# PowerDistribution.net
KiCad netlist of a schematic drawn in Altium Designer
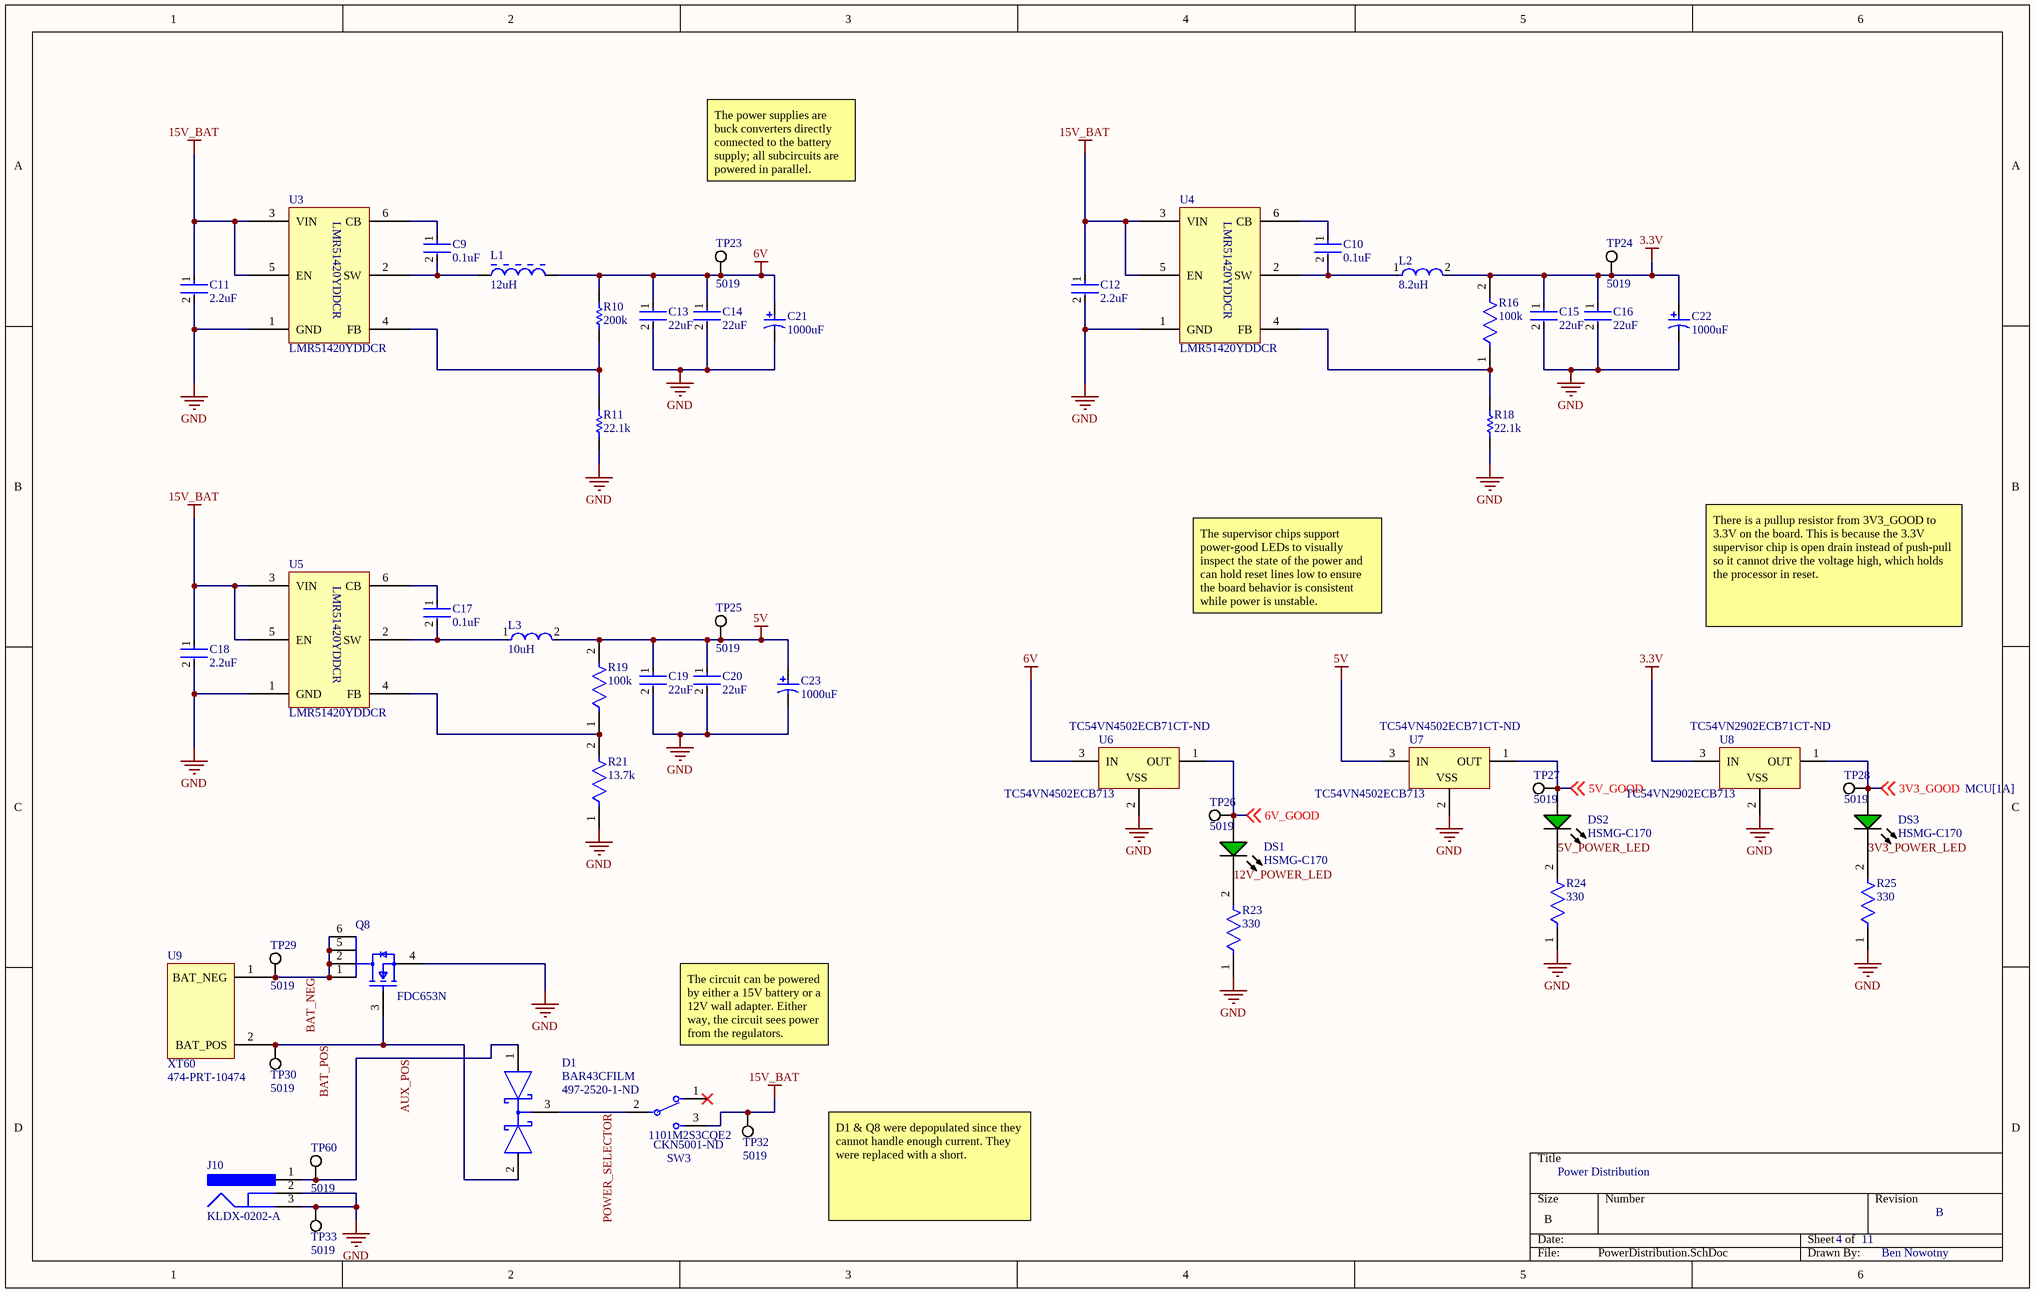
[diagram p0: PowerDistribution.SchDoc]

(export (version "E")
  (design (tool "Eeschema 10.0.6"))
  (components
    (comp (ref "C9")
      (value "0.1uF")
      (footprint "FP-CC0805-0_85-MFG")
      (description "CAP CER 0.1UF 25V X7R 0805")
      (fields (field (name "MANUFACTURER PART NUMBER") "CC0805KRX7R8BB104") (field (name "TOLERANCE") "0.1"))
      (libsource (lib "Altium Content Vault") (part "11868f565c42a9108669ba33697ecf6"))
    )
    (comp (ref "C10")
      (value "0.1uF")
      (footprint "FP-CC0805-0_85-MFG")
      (description "CAP CER 0.1UF 25V X7R 0805")
      (fields (field (name "MANUFACTURER PART NUMBER") "CC0805KRX7R8BB104") (field (name "TOLERANCE") "0.1"))
      (libsource (lib "Altium Content Vault") (part "11868f565c42a9108669ba33697ecf6"))
    )
    (comp (ref "C11")
      (value "2.2uF")
      (footprint "FP-CGA4J-IPC_A")
      (description "Cap Ceramic 2.2uF 35V X7R 10% Pad SMD 0805 +125°C Automotive T/R")
      (fields (field (name "TOLERANCE") "10%") (field (name "MANUFACTURER") "TDK"))
      (libsource (lib "Altium Content Vault") (part "b4654b650e69147ec39a6b967a45e02"))
    )
    (comp (ref "C12")
      (value "2.2uF")
      (footprint "FP-CGA4J-IPC_A")
      (description "Cap Ceramic 2.2uF 35V X7R 10% Pad SMD 0805 +125°C Automotive T/R")
      (fields (field (name "TOLERANCE") "10%") (field (name "MANUFACTURER") "TDK"))
      (libsource (lib "Altium Content Vault") (part "b4654b650e69147ec39a6b967a45e02"))
    )
    (comp (ref "C13")
      (value "22uF")
      (footprint "FP-GRM21B-0_2-e0_2_0_7-IPC_B")
      (description "Chip Multilayer Ceramic Capacitors for General Purpose, 0805, 22uF, X5R, 15%, 20%, 25V")
      (fields (field (name "TOLERANCE") "20%") (field (name "VOLTAGE") "25V"))
      (libsource (lib "Altium Content Vault") (part "b4654b650e69147ec39a6b967a45e02"))
    )
    (comp (ref "C14")
      (value "22uF")
      (footprint "FP-GRM21B-0_2-e0_2_0_7-IPC_B")
      (description "Chip Multilayer Ceramic Capacitors for General Purpose, 0805, 22uF, X5R, 15%, 20%, 25V")
      (fields (field (name "TOLERANCE") "20%") (field (name "VOLTAGE") "25V"))
      (libsource (lib "Altium Content Vault") (part "b4654b650e69147ec39a6b967a45e02"))
    )
    (comp (ref "C15")
      (value "22uF")
      (footprint "FP-GRM21B-0_2-e0_2_0_7-IPC_B")
      (description "Chip Multilayer Ceramic Capacitors for General Purpose, 0805, 22uF, X5R, 15%, 20%, 25V")
      (fields (field (name "TOLERANCE") "20%") (field (name "VOLTAGE") "25V"))
      (libsource (lib "Altium Content Vault") (part "b4654b650e69147ec39a6b967a45e02"))
    )
    (comp (ref "C16")
      (value "22uF")
      (footprint "FP-GRM21B-0_2-e0_2_0_7-IPC_B")
      (description "Chip Multilayer Ceramic Capacitors for General Purpose, 0805, 22uF, X5R, 15%, 20%, 25V")
      (fields (field (name "TOLERANCE") "20%") (field (name "VOLTAGE") "25V"))
      (libsource (lib "Altium Content Vault") (part "b4654b650e69147ec39a6b967a45e02"))
    )
    (comp (ref "C17")
      (value "0.1uF")
      (footprint "FP-CC0805-0_85-MFG")
      (description "CAP CER 0.1UF 25V X7R 0805")
      (fields (field (name "MANUFACTURER PART NUMBER") "CC0805KRX7R8BB104") (field (name "TOLERANCE") "0.1"))
      (libsource (lib "Altium Content Vault") (part "11868f565c42a9108669ba33697ecf6"))
    )
    (comp (ref "C18")
      (value "2.2uF")
      (footprint "FP-CGA4J-IPC_A")
      (description "Cap Ceramic 2.2uF 35V X7R 10% Pad SMD 0805 +125°C Automotive T/R")
      (fields (field (name "TOLERANCE") "10%") (field (name "MANUFACTURER") "TDK"))
      (libsource (lib "Altium Content Vault") (part "b4654b650e69147ec39a6b967a45e02"))
    )
    (comp (ref "C19")
      (value "22uF")
      (footprint "FP-GRM21B-0_2-e0_2_0_7-IPC_B")
      (description "Chip Multilayer Ceramic Capacitors for General Purpose, 0805, 22uF, X5R, 15%, 20%, 25V")
      (fields (field (name "TOLERANCE") "20%") (field (name "VOLTAGE") "25V"))
      (libsource (lib "Altium Content Vault") (part "b4654b650e69147ec39a6b967a45e02"))
    )
    (comp (ref "C20")
      (value "22uF")
      (footprint "FP-GRM21B-0_2-e0_2_0_7-IPC_B")
      (description "Chip Multilayer Ceramic Capacitors for General Purpose, 0805, 22uF, X5R, 15%, 20%, 25V")
      (fields (field (name "TOLERANCE") "20%") (field (name "VOLTAGE") "25V"))
      (libsource (lib "Altium Content Vault") (part "b4654b650e69147ec39a6b967a45e02"))
    )
    (comp (ref "C21")
      (value "1000uF")
      (footprint "NIC-CAPA2-10X10_V")
      (fields
        (field (name "MANUFACTURER") "Nichicon")
        (field (name "PARTNUMBER") "UUD1A102MNL1GS")
        (field (name "TOLERANCE") "20%")
      )
      (libsource (lib "Altium Content Vault") (part "NIC-CAP-P-2"))
    )
    (comp (ref "C22")
      (value "1000uF")
      (footprint "NIC-CAPA2-10X10_V")
      (fields
        (field (name "MANUFACTURER") "Nichicon")
        (field (name "PARTNUMBER") "UUD1A102MNL1GS")
        (field (name "TOLERANCE") "20%")
      )
      (libsource (lib "Altium Content Vault") (part "NIC-CAP-P-2"))
    )
    (comp (ref "C23")
      (value "1000uF")
      (footprint "NIC-CAPA2-10X10_V")
      (fields
        (field (name "MANUFACTURER") "Nichicon")
        (field (name "PARTNUMBER") "UUD1A102MNL1GS")
        (field (name "TOLERANCE") "20%")
      )
      (libsource (lib "Altium Content Vault") (part "NIC-CAP-P-2"))
    )
    (comp (ref "D1")
      (value "BAR43CFILM")
      (footprint "FP-SOT23-3L-MFG")
      (description "DIODE ARRAY SCHOTTKY 30V SOT23-3")
      (fields
        (field (name "OCTOPART") "https://octopart.com/bar43cfilm-stmicroelectronics-39683191")
        (field (name "MANUFACTURER") "STMicroelectronics")
        (field (name "SUPPLIER PART NUMBER 1") "497-2520-1-ND")
      )
      (libsource (lib "Altium Content Vault") (part "680c0165bcb2da9b6dd4f4f2387c35b"))
    )
    (comp (ref "DS1")
      (value "HSMG-C170")
      (footprint "AVAG-HSMX-C170_V")
      (description "Chip LED, Green, 2.2 V, -40 to 85 degC, 2-Pin SMD, Pb-Free, Tape and Reel")
      (fields (field (name "MANUFACTURER") "Avago"))
      (libsource (lib "Altium Content Vault") (part "LED_GREEN_A1K2-2"))
    )
    (comp (ref "DS2")
      (value "HSMG-C170")
      (footprint "AVAG-HSMX-C170_V")
      (description "Chip LED, Green, 2.2 V, -40 to 85 degC, 2-Pin SMD, Pb-Free, Tape and Reel")
      (fields (field (name "MANUFACTURER") "Avago"))
      (libsource (lib "Altium Content Vault") (part "LED_GREEN_A1K2-2"))
    )
    (comp (ref "DS3")
      (value "HSMG-C170")
      (footprint "AVAG-HSMX-C170_V")
      (description "Chip LED, Green, 2.2 V, -40 to 85 degC, 2-Pin SMD, Pb-Free, Tape and Reel")
      (fields (field (name "MANUFACTURER") "Avago"))
      (libsource (lib "Altium Content Vault") (part "LED_GREEN_A1K2-2"))
    )
    (comp (ref "J10")
      (value "KLDX-0202-A")
      (footprint "KYCN-KLDX-0202-A_V")
      (description "DC Power Jack, 24 V, 3.5 A, -25 to 85 degC, 3-Pin THD, RoHS")
      (fields (field (name "MANUFACTURER") "Kycon"))
      (libsource (lib "Altium Content Vault") (part "JACK-2CD3-RN"))
    )
    (comp (ref "L1")
      (value "12uH")
      (footprint "BOUR-SDR0403-2_V")
      (fields
        (field (name "PARTNUMBER") "SDR0403-120ML")
        (field (name "MANUFACTURER") "Bourns")
        (field (name "TOLERANCE") "20%")
      )
      (libsource (lib "Altium Content Vault") (part "BOUR-IND-2A"))
    )
    (comp (ref "L2")
      (value "8.2uH")
      (footprint "FP-SRP4020TA-MFG")
      (description "FIXED IND 8.2UH 2A 180 MOHM SMD")
      (fields (field (name "MANUFACTURER") "Bourns") (field (name "TOLERANCE") "20%"))
      (libsource (lib "Altium Content Vault") (part "725321dda6339637d4d059423bc1c3c"))
    )
    (comp (ref "L3")
      (value "10uH")
      (footprint "FP-LB2012-1_25-0_2-MFG")
      (description "SMD Inductors 10uH ±10% 0.15A 0.468Ω 0805")
      (fields (field (name "TOLERANCE") "10%") (field (name "MANUFACTURER") "Taiyo Yuden"))
      (libsource (lib "Altium Content Vault") (part "725321dda6339637d4d059423bc1c3c"))
    )
    (comp (ref "Q8")
      (value "FDC653N")
      (footprint "FP-419BL-MFG")
      (description "MOSFET N-CH 30V 5A SSOT-6")
      (fields
        (field (name "MANUFACTURER") "ON Semiconductor")
        (field (name "OCTOPART") "https://octopart.com/fdc653n-on+semiconductor-84325763")
      )
      (libsource (lib "Altium Content Vault") (part "564475a1266d674ca215bf0a31b2b4c"))
    )
    (comp (ref "R10")
      (value "200k")
      (footprint "RESC2013X50X30NL20T20")
      (fields
        (field (name "PART NUMBER") "CRCW0805200KFKEA")
        (field (name "MANUFACTURER") "Vishay Dale")
        (field (name "TOLERANCE") "1%")
      )
      (libsource (lib "Altium Content Vault") (part "RES"))
    )
    (comp (ref "R11")
      (value "22.1k")
      (footprint "RESC2013X70X40NL20T20")
      (fields
        (field (name "PART NUMBER") "ERJ-6ENF2212V")
        (field (name "MANUFACTURER") "Panasonic")
        (field (name "TOLERANCE") "1%")
      )
      (libsource (lib "Altium Content Vault") (part "RES"))
    )
    (comp (ref "R16")
      (value "100k")
      (footprint "FP-RC0805-0_6-IPC_C")
      (description "RES 100K OHM 1% 1/8W 0805")
      (fields (field (name "TOLERANCE") "1%") (field (name "MANUFACTURER") "Yageo"))
      (libsource (lib "Altium Content Vault") (part "1029c3af85768c4190bb7ad29bc67b5"))
    )
    (comp (ref "R18")
      (value "22.1k")
      (footprint "RESC2013X70X40NL20T20")
      (fields
        (field (name "PART NUMBER") "ERJ-6ENF2212V")
        (field (name "MANUFACTURER") "Panasonic")
        (field (name "TOLERANCE") "1%")
      )
      (libsource (lib "Altium Content Vault") (part "RES"))
    )
    (comp (ref "R19")
      (value "100k")
      (footprint "FP-RC0805-0_6-IPC_C")
      (description "RES 100K OHM 1% 1/8W 0805")
      (fields (field (name "TOLERANCE") "1%") (field (name "MANUFACTURER") "Yageo"))
      (libsource (lib "Altium Content Vault") (part "1029c3af85768c4190bb7ad29bc67b5"))
    )
    (comp (ref "R21")
      (value "13.7k")
      (footprint "FP-CRCW0805-e3-IPC_A")
      (description "RES Thick Film, 13.7kΩ, 1%, 0.125W, 100ppm/°C, 0805")
      (fields (field (name "TOLERANCE") "1%") (field (name "MANUFACTURER") "Vishay"))
      (libsource (lib "Altium Content Vault") (part "1029c3af85768c4190bb7ad29bc67b5"))
    )
    (comp (ref "R23")
      (value "330")
      (footprint "FP-CRCW0805-e3-MFG")
      (description "RES Thick Film, 330Ω, 1%, 0.125W, 100ppm/°C, 0805")
      (fields (field (name "TOLERANCE") "1%") (field (name "MANUFACTURER") "Vishay"))
      (libsource (lib "Altium Content Vault") (part "1029c3af85768c4190bb7ad29bc67b5"))
    )
    (comp (ref "R24")
      (value "330")
      (footprint "FP-CRCW0805-e3-MFG")
      (description "RES Thick Film, 330Ω, 1%, 0.125W, 100ppm/°C, 0805")
      (fields (field (name "TOLERANCE") "1%") (field (name "MANUFACTURER") "Vishay"))
      (libsource (lib "Altium Content Vault") (part "1029c3af85768c4190bb7ad29bc67b5"))
    )
    (comp (ref "R25")
      (value "330")
      (footprint "FP-CRCW0805-e3-MFG")
      (description "RES Thick Film, 330Ω, 1%, 0.125W, 100ppm/°C, 0805")
      (fields (field (name "TOLERANCE") "1%") (field (name "MANUFACTURER") "Vishay"))
      (libsource (lib "Altium Content Vault") (part "1029c3af85768c4190bb7ad29bc67b5"))
    )
    (comp (ref "SW3")
      (value "1101M2S3CQE2")
      (footprint "FP-1101M2S3CQE2-MFG")
      (description "SWITCH SLIDE SPDT 6A 120V")
      (fields (field (name "SUPPLIER PART NUMBER 1") "CKN5001-ND") (field (name "MANUFACTURER") "ITT C&K"))
      (libsource (lib "Altium Content Vault") (part "7fcaa069a19c2acd609832313418d7c"))
    )
    (comp (ref "TP23")
      (value "5019")
      (footprint "KSTN-5019_V")
      (description "Test Point, 1 Position SMD, RoHS, Tape and Reel")
      (fields (field (name "MANUFACTURER") "Keystone Electronics"))
      (libsource (lib "Altium Content Vault") (part "TESTPOINT_WHITE"))
    )
    (comp (ref "TP24")
      (value "5019")
      (footprint "KSTN-5019_V")
      (description "Test Point, 1 Position SMD, RoHS, Tape and Reel")
      (fields (field (name "MANUFACTURER") "Keystone Electronics"))
      (libsource (lib "Altium Content Vault") (part "TESTPOINT_WHITE"))
    )
    (comp (ref "TP25")
      (value "5019")
      (footprint "KSTN-5019_V")
      (description "Test Point, 1 Position SMD, RoHS, Tape and Reel")
      (fields (field (name "MANUFACTURER") "Keystone Electronics"))
      (libsource (lib "Altium Content Vault") (part "TESTPOINT_WHITE"))
    )
    (comp (ref "TP26")
      (value "5019")
      (footprint "KSTN-5019_V")
      (description "Test Point, 1 Position SMD, RoHS, Tape and Reel")
      (fields (field (name "MANUFACTURER") "Keystone Electronics"))
      (libsource (lib "Altium Content Vault") (part "TESTPOINT_WHITE"))
    )
    (comp (ref "TP27")
      (value "5019")
      (footprint "KSTN-5019_V")
      (description "Test Point, 1 Position SMD, RoHS, Tape and Reel")
      (fields (field (name "MANUFACTURER") "Keystone Electronics"))
      (libsource (lib "Altium Content Vault") (part "TESTPOINT_WHITE"))
    )
    (comp (ref "TP28")
      (value "5019")
      (footprint "KSTN-5019_V")
      (description "Test Point, 1 Position SMD, RoHS, Tape and Reel")
      (fields (field (name "MANUFACTURER") "Keystone Electronics"))
      (libsource (lib "Altium Content Vault") (part "TESTPOINT_WHITE"))
    )
    (comp (ref "TP29")
      (value "5019")
      (footprint "KSTN-5019_V")
      (description "Test Point, 1 Position SMD, RoHS, Tape and Reel")
      (fields (field (name "MANUFACTURER") "Keystone Electronics"))
      (libsource (lib "Altium Content Vault") (part "TESTPOINT_WHITE"))
    )
    (comp (ref "TP30")
      (value "5019")
      (footprint "KSTN-5019_V")
      (description "Test Point, 1 Position SMD, RoHS, Tape and Reel")
      (fields (field (name "MANUFACTURER") "Keystone Electronics"))
      (libsource (lib "Altium Content Vault") (part "TESTPOINT_WHITE"))
    )
    (comp (ref "TP32")
      (value "5019")
      (footprint "KSTN-5019_V")
      (description "Test Point, 1 Position SMD, RoHS, Tape and Reel")
      (fields (field (name "MANUFACTURER") "Keystone Electronics"))
      (libsource (lib "Altium Content Vault") (part "TESTPOINT_WHITE"))
    )
    (comp (ref "TP33")
      (value "5019")
      (footprint "KSTN-5019_V")
      (description "Test Point, 1 Position SMD, RoHS, Tape and Reel")
      (fields (field (name "MANUFACTURER") "Keystone Electronics"))
      (libsource (lib "Altium Content Vault") (part "TESTPOINT_WHITE"))
    )
    (comp (ref "TP60")
      (value "5019")
      (footprint "KSTN-5019_V")
      (description "Test Point, 1 Position SMD, RoHS, Tape and Reel")
      (fields (field (name "MANUFACTURER") "Keystone Electronics"))
      (libsource (lib "Altium Content Vault") (part "TESTPOINT_WHITE"))
    )
    (comp (ref "U3")
      (value "LMR51420YDDCR")
      (footprint "BUCK_REG_FOOTPRINT_SOT95P280X110-6N")
      (fields (field (name "MANUFACTURER") "Texas Instruments"))
      (libsource (lib "CustomSchematics") (part "LMR51420YDDCR"))
    )
    (comp (ref "U4")
      (value "LMR51420YDDCR")
      (footprint "BUCK_REG_FOOTPRINT_SOT95P280X110-6N")
      (fields (field (name "MANUFACTURER") "Texas Instruments"))
      (libsource (lib "CustomSchematics") (part "LMR51420YDDCR"))
    )
    (comp (ref "U5")
      (value "LMR51420YDDCR")
      (footprint "BUCK_REG_FOOTPRINT_SOT95P280X110-6N")
      (fields (field (name "MANUFACTURER") "Texas Instruments"))
      (libsource (lib "CustomSchematics") (part "LMR51420YDDCR"))
    )
    (comp (ref "U6")
      (value "TC54VN4502ECB713")
      (footprint "SOT-23A-CB3_L")
      (fields
        (field (name "SUPPLIER PART NUMBER 1") "TC54VN4502ECB71CT-ND")
        (field (name "MANUFACTURER") "Microchip")
      )
      (libsource (lib "Altium Content Vault") (part "PM-VLTD-TC51N2202-SOT3"))
    )
    (comp (ref "U7")
      (value "TC54VN4502ECB713")
      (footprint "SOT-23A-CB3_L")
      (fields
        (field (name "SUPPLIER PART NUMBER 1") "TC54VN4502ECB71CT-ND")
        (field (name "MANUFACTURER") "Microchip")
      )
      (libsource (lib "Altium Content Vault") (part "PM-VLTD-TC51N2202-SOT3"))
    )
    (comp (ref "U8")
      (value "TC54VN2902ECB713")
      (footprint "SOT-23A-CB3_L")
      (fields
        (field (name "SUPPLIER PART NUMBER 1") "TC54VN2902ECB71CT-ND")
        (field (name "MANUFACTURER") "Microchip")
      )
      (libsource (lib "Altium Content Vault") (part "PM-VLTD-TC51N2202-SOT3"))
    )
    (comp (ref "U9")
      (value "XT60")
      (footprint "XT60")
      (description "XT60 Connectors Male/female Pair")
      (fields
        (field (name "MANUFACTURER") "SparkFun")
        (field (name "MANUFACTURER PART NUMBER") "PRT-10474")
        (field (name "SUPPLIER PART NUMBER 1") "474-PRT-10474")
      )
      (libsource (lib "CustomSchematics") (part "XT60"))
    )
  )
  (nets
    (net (code "1") (name "/3V3_POWER_LED") (class "Default")
      (node (ref "DS3") (pin "2") (pinfunction "K_2") (pintype "passive"))
      (node (ref "R25") (pin "2") (pinfunction "2_2") (pintype "passive"))
    )
    (net (code "2") (name "/5V_POWER_LED") (class "Default")
      (node (ref "DS2") (pin "2") (pinfunction "K_2") (pintype "passive"))
      (node (ref "R24") (pin "2") (pinfunction "2_2") (pintype "passive"))
    )
    (net (code "3") (name "/12V_POWER_LED") (class "Default")
      (node (ref "DS1") (pin "2") (pinfunction "K_2") (pintype "passive"))
      (node (ref "R23") (pin "2") (pinfunction "2_2") (pintype "passive"))
    )
    (net (code "4") (name "/AUX_POS") (class "Default")
      (node (ref "D1") (pin "1") (pinfunction "A1_1") (pintype "passive"))
      (node (ref "J10") (pin "1") (pinfunction "1_1") (pintype "passive"))
      (node (ref "TP60") (pin "1") (pinfunction "1_1") (pintype "passive"))
    )
    (net (code "5") (name "/BAT_NEG") (class "Default")
      (node (ref "Q8") (pin "1") (pinfunction "D_1") (pintype "passive"))
      (node (ref "Q8") (pin "2") (pinfunction "D_2") (pintype "passive"))
      (node (ref "Q8") (pin "5") (pinfunction "D_5") (pintype "passive"))
      (node (ref "Q8") (pin "6") (pinfunction "D_6") (pintype "passive"))
      (node (ref "TP29") (pin "1") (pinfunction "1_1") (pintype "passive"))
      (node (ref "U9") (pin "1") (pinfunction "BAT_NEG_1") (pintype "passive"))
    )
    (net (code "6") (name "/BAT_POS") (class "Default")
      (node (ref "D1") (pin "2") (pinfunction "A2_2") (pintype "passive"))
      (node (ref "Q8") (pin "3") (pinfunction "G_3") (pintype "passive"))
      (node (ref "TP30") (pin "1") (pinfunction "1_1") (pintype "passive"))
      (node (ref "U9") (pin "2") (pinfunction "BAT_POS_2") (pintype "passive"))
    )
    (net (code "7") (name "/POWER_SELECTOR") (class "Default")
      (node (ref "D1") (pin "3") (pinfunction "K_3") (pintype "passive"))
      (node (ref "SW3") (pin "2") (pinfunction "COMM_2") (pintype "passive"))
    )
    (net (code "8") (name "3.3V") (class "Default")
      (node (ref "C15") (pin "1") (pinfunction "1_1") (pintype "passive"))
      (node (ref "C16") (pin "1") (pinfunction "1_1") (pintype "passive"))
      (node (ref "C22") (pin "1") (pinfunction "1_1") (pintype "passive"))
      (node (ref "L2") (pin "2") (pinfunction "2_2") (pintype "passive"))
      (node (ref "R16") (pin "2") (pinfunction "2_2") (pintype "passive"))
      (node (ref "TP24") (pin "1") (pinfunction "1_1") (pintype "passive"))
      (node (ref "U8") (pin "3") (pinfunction "IN_3") (pintype "power_in"))
    )
    (net (code "9") (name "3V3_GOOD") (class "Default")
      (node (ref "DS3") (pin "1") (pinfunction "A_1") (pintype "passive"))
      (node (ref "TP28") (pin "1") (pinfunction "1_1") (pintype "passive"))
      (node (ref "U8") (pin "1") (pinfunction "OUT_1") (pintype "power_in"))
    )
    (net (code "10") (name "5V") (class "Default")
      (node (ref "C19") (pin "1") (pinfunction "1_1") (pintype "passive"))
      (node (ref "C20") (pin "1") (pinfunction "1_1") (pintype "passive"))
      (node (ref "C23") (pin "1") (pinfunction "1_1") (pintype "passive"))
      (node (ref "L3") (pin "2") (pinfunction "2_2") (pintype "passive"))
      (node (ref "R19") (pin "2") (pinfunction "2_2") (pintype "passive"))
      (node (ref "TP25") (pin "1") (pinfunction "1_1") (pintype "passive"))
      (node (ref "U7") (pin "3") (pinfunction "IN_3") (pintype "power_in"))
    )
    (net (code "11") (name "5V_GOOD") (class "Default")
      (node (ref "DS2") (pin "1") (pinfunction "A_1") (pintype "passive"))
      (node (ref "TP27") (pin "1") (pinfunction "1_1") (pintype "passive"))
      (node (ref "U7") (pin "1") (pinfunction "OUT_1") (pintype "power_in"))
    )
    (net (code "12") (name "6V") (class "Default")
      (node (ref "C13") (pin "1") (pinfunction "1_1") (pintype "passive"))
      (node (ref "C14") (pin "1") (pinfunction "1_1") (pintype "passive"))
      (node (ref "C21") (pin "1") (pinfunction "1_1") (pintype "passive"))
      (node (ref "L1") (pin "2") (pinfunction "2_2") (pintype "passive"))
      (node (ref "R10") (pin "2") (pinfunction "2_2") (pintype "passive"))
      (node (ref "TP23") (pin "1") (pinfunction "1_1") (pintype "passive"))
      (node (ref "U6") (pin "3") (pinfunction "IN_3") (pintype "power_in"))
    )
    (net (code "13") (name "6V_GOOD") (class "Default")
      (node (ref "DS1") (pin "1") (pinfunction "A_1") (pintype "passive"))
      (node (ref "TP26") (pin "1") (pinfunction "1_1") (pintype "passive"))
      (node (ref "U6") (pin "1") (pinfunction "OUT_1") (pintype "power_in"))
    )
    (net (code "14") (name "15V_BAT") (class "Default")
      (node (ref "C11") (pin "1") (pinfunction "1_1") (pintype "passive"))
      (node (ref "C12") (pin "1") (pinfunction "1_1") (pintype "passive"))
      (node (ref "C18") (pin "1") (pinfunction "1_1") (pintype "passive"))
      (node (ref "SW3") (pin "3") (pinfunction "3_3") (pintype "passive"))
      (node (ref "TP32") (pin "1") (pinfunction "1_1") (pintype "passive"))
      (node (ref "U3") (pin "3") (pinfunction "VIN_3") (pintype "passive"))
      (node (ref "U3") (pin "5") (pinfunction "EN_5") (pintype "passive"))
      (node (ref "U4") (pin "3") (pinfunction "VIN_3") (pintype "passive"))
      (node (ref "U4") (pin "5") (pinfunction "EN_5") (pintype "passive"))
      (node (ref "U5") (pin "3") (pinfunction "VIN_3") (pintype "passive"))
      (node (ref "U5") (pin "5") (pinfunction "EN_5") (pintype "passive"))
    )
    (net (code "15") (name "GND") (class "Default")
      (node (ref "C11") (pin "2") (pinfunction "2_2") (pintype "passive"))
      (node (ref "C12") (pin "2") (pinfunction "2_2") (pintype "passive"))
      (node (ref "C13") (pin "2") (pinfunction "2_2") (pintype "passive"))
      (node (ref "C14") (pin "2") (pinfunction "2_2") (pintype "passive"))
      (node (ref "C15") (pin "2") (pinfunction "2_2") (pintype "passive"))
      (node (ref "C16") (pin "2") (pinfunction "2_2") (pintype "passive"))
      (node (ref "C18") (pin "2") (pinfunction "2_2") (pintype "passive"))
      (node (ref "C19") (pin "2") (pinfunction "2_2") (pintype "passive"))
      (node (ref "C20") (pin "2") (pinfunction "2_2") (pintype "passive"))
      (node (ref "C21") (pin "2") (pinfunction "2_2") (pintype "passive"))
      (node (ref "C22") (pin "2") (pinfunction "2_2") (pintype "passive"))
      (node (ref "C23") (pin "2") (pinfunction "2_2") (pintype "passive"))
      (node (ref "J10") (pin "2") (pinfunction "2_2") (pintype "passive"))
      (node (ref "J10") (pin "3") (pinfunction "3_3") (pintype "passive"))
      (node (ref "Q8") (pin "4") (pinfunction "S_4") (pintype "passive"))
      (node (ref "R11") (pin "1") (pinfunction "1_1") (pintype "passive"))
      (node (ref "R18") (pin "1") (pinfunction "1_1") (pintype "passive"))
      (node (ref "R21") (pin "1") (pinfunction "1_1") (pintype "passive"))
      (node (ref "R23") (pin "1") (pinfunction "1_1") (pintype "passive"))
      (node (ref "R24") (pin "1") (pinfunction "1_1") (pintype "passive"))
      (node (ref "R25") (pin "1") (pinfunction "1_1") (pintype "passive"))
      (node (ref "TP33") (pin "1") (pinfunction "1_1") (pintype "passive"))
      (node (ref "U3") (pin "1") (pinfunction "GND_1") (pintype "passive"))
      (node (ref "U4") (pin "1") (pinfunction "GND_1") (pintype "passive"))
      (node (ref "U5") (pin "1") (pinfunction "GND_1") (pintype "passive"))
      (node (ref "U6") (pin "2") (pinfunction "VSS_2") (pintype "power_in"))
      (node (ref "U7") (pin "2") (pinfunction "VSS_2") (pintype "power_in"))
      (node (ref "U8") (pin "2") (pinfunction "VSS_2") (pintype "power_in"))
    )
    (net (code "16") (name "Net-(U3-CB)") (class "Default")
      (node (ref "C9") (pin "1") (pinfunction "1_1") (pintype "passive"))
      (node (ref "U3") (pin "6") (pinfunction "CB_6") (pintype "passive"))
    )
    (net (code "17") (name "Net-(U3-FB)") (class "Default")
      (node (ref "R10") (pin "1") (pinfunction "1_1") (pintype "passive"))
      (node (ref "R11") (pin "2") (pinfunction "2_2") (pintype "passive"))
      (node (ref "U3") (pin "4") (pinfunction "FB_4") (pintype "passive"))
    )
    (net (code "18") (name "Net-(U3-SW)") (class "Default")
      (node (ref "C9") (pin "2") (pinfunction "2_2") (pintype "passive"))
      (node (ref "L1") (pin "1") (pinfunction "1_1") (pintype "passive"))
      (node (ref "U3") (pin "2") (pinfunction "SW_2") (pintype "passive"))
    )
    (net (code "19") (name "Net-(U4-CB)") (class "Default")
      (node (ref "C10") (pin "1") (pinfunction "1_1") (pintype "passive"))
      (node (ref "U4") (pin "6") (pinfunction "CB_6") (pintype "passive"))
    )
    (net (code "20") (name "Net-(U4-FB)") (class "Default")
      (node (ref "R16") (pin "1") (pinfunction "1_1") (pintype "passive"))
      (node (ref "R18") (pin "2") (pinfunction "2_2") (pintype "passive"))
      (node (ref "U4") (pin "4") (pinfunction "FB_4") (pintype "passive"))
    )
    (net (code "21") (name "Net-(U4-SW)") (class "Default")
      (node (ref "C10") (pin "2") (pinfunction "2_2") (pintype "passive"))
      (node (ref "L2") (pin "1") (pinfunction "1_1") (pintype "passive"))
      (node (ref "U4") (pin "2") (pinfunction "SW_2") (pintype "passive"))
    )
    (net (code "22") (name "Net-(U5-CB)") (class "Default")
      (node (ref "C17") (pin "1") (pinfunction "1_1") (pintype "passive"))
      (node (ref "U5") (pin "6") (pinfunction "CB_6") (pintype "passive"))
    )
    (net (code "23") (name "Net-(U5-FB)") (class "Default")
      (node (ref "R19") (pin "1") (pinfunction "1_1") (pintype "passive"))
      (node (ref "R21") (pin "2") (pinfunction "2_2") (pintype "passive"))
      (node (ref "U5") (pin "4") (pinfunction "FB_4") (pintype "passive"))
    )
    (net (code "24") (name "Net-(U5-SW)") (class "Default")
      (node (ref "C17") (pin "2") (pinfunction "2_2") (pintype "passive"))
      (node (ref "L3") (pin "1") (pinfunction "1_1") (pintype "passive"))
      (node (ref "U5") (pin "2") (pinfunction "SW_2") (pintype "passive"))
    )
    (net (code "25") (name "unconnected-(SW3-Pad1)") (class "Default")
      (node (ref "SW3") (pin "1") (pinfunction "1_1") (pintype "passive+no_connect"))
    )
  )
)
